# remote_display.net
KiCad netlist of a schematic drawn in EAGLE
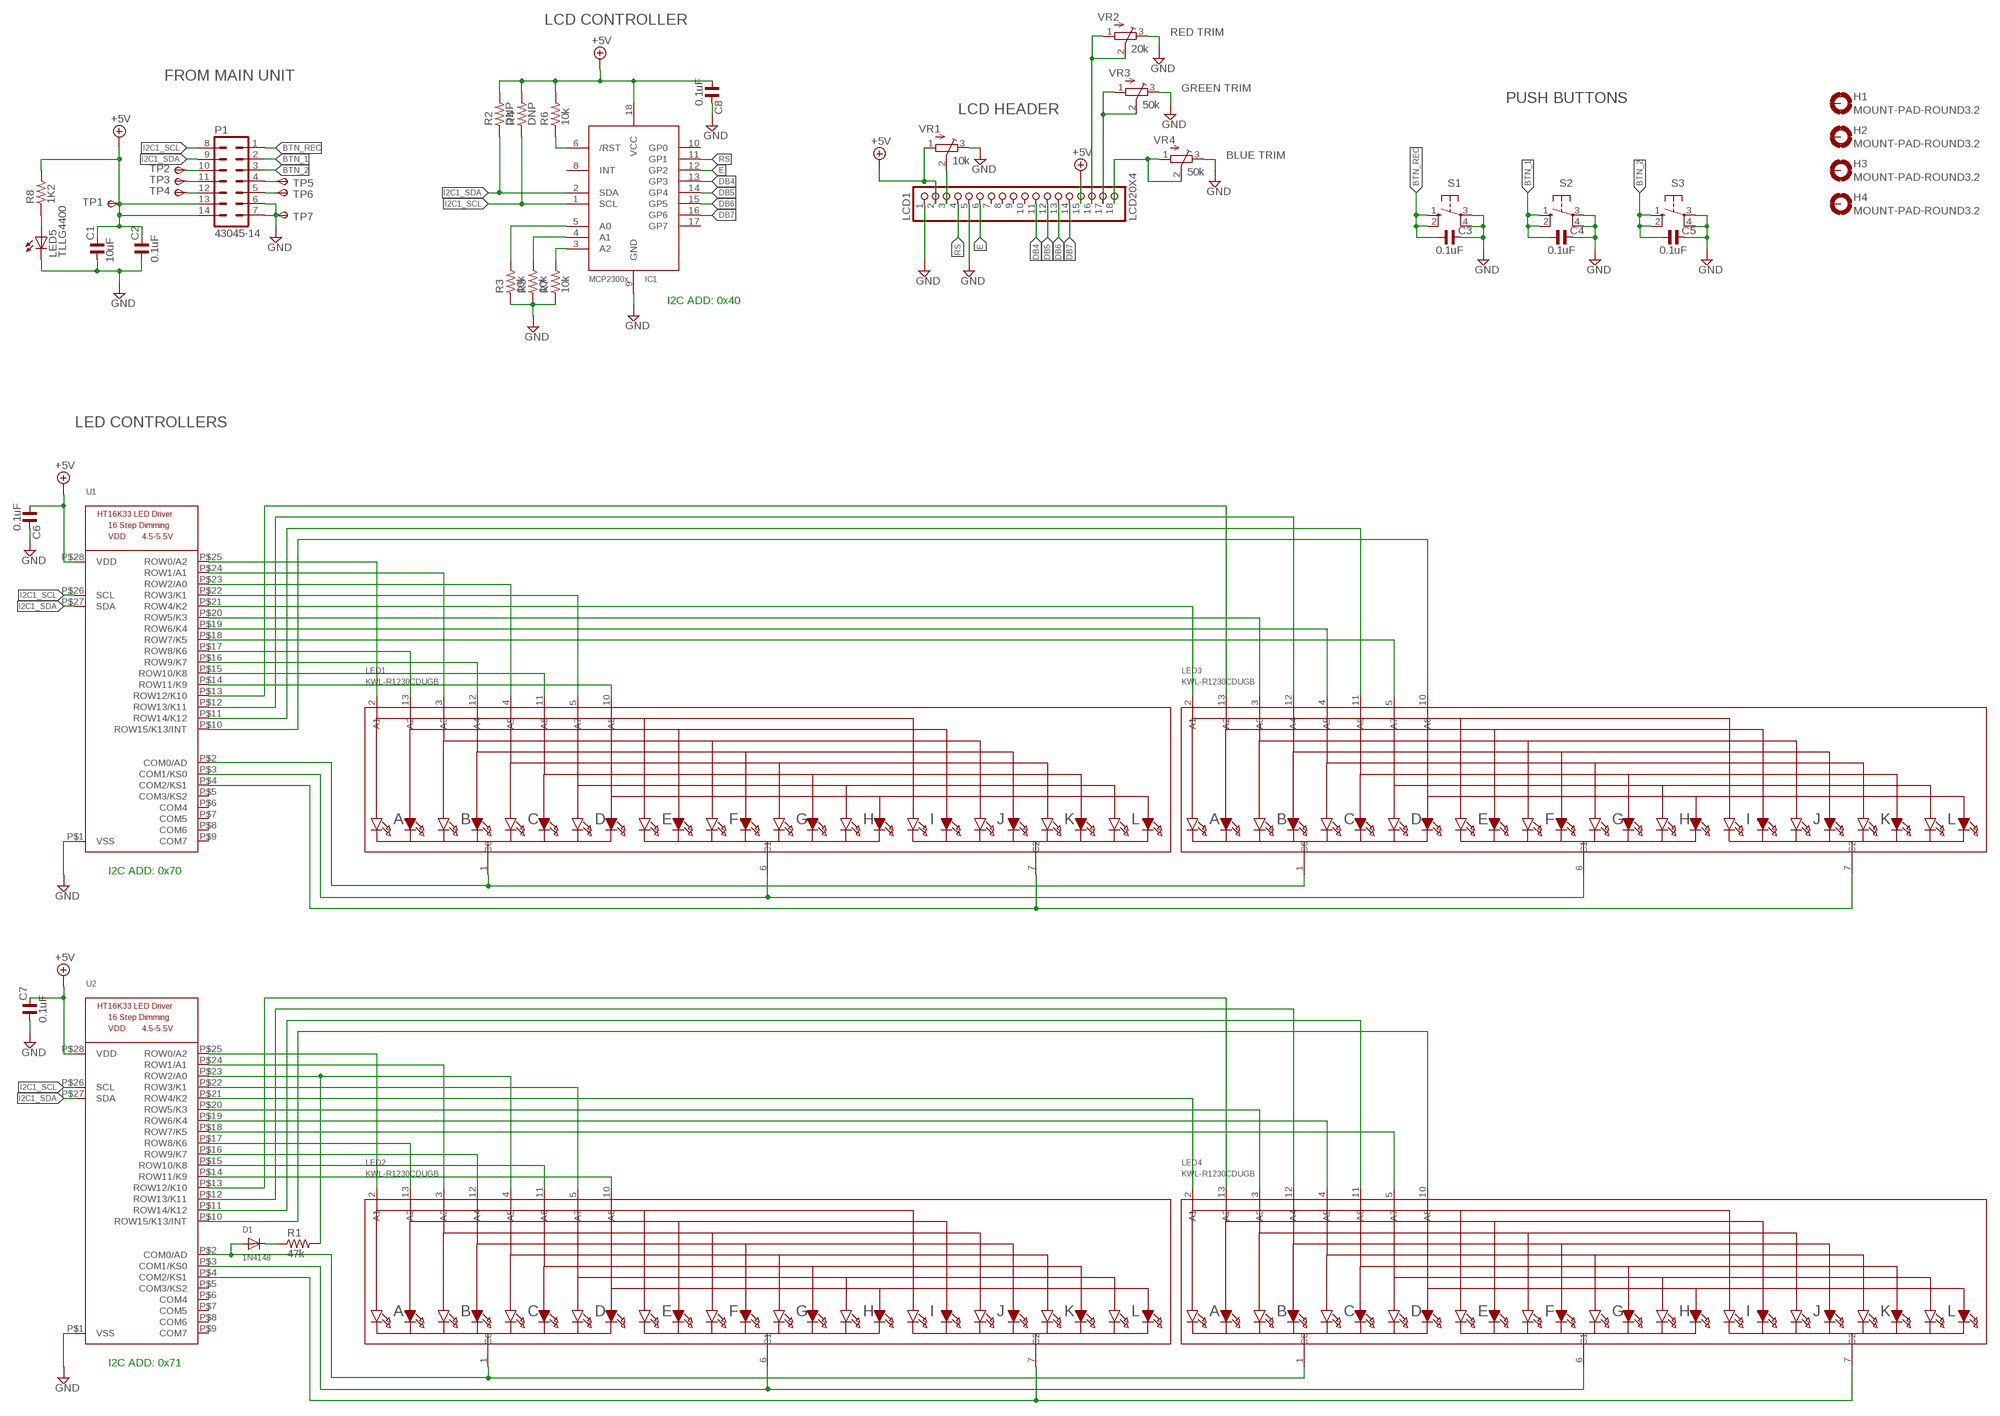
[diagram p0: schematic, sheet 1]

(export (version "E")
  (design (tool "Eeschema 10.0.6"))
  (components
    (comp (ref "C1")
      (value "10uF")
      (footprint "eagle-import:C0805")
      (fields (field (name "MPN") "C2012X5R1E106K125AB"))
      (libsource (lib "eagle-import") (part "C_0805"))
    )
    (comp (ref "C2")
      (value "0.1uF")
      (footprint "eagle-import:C0805")
      (fields (field (name "MPN") "C2012X7R1H104K085AA"))
      (libsource (lib "eagle-import") (part "C_0805"))
    )
    (comp (ref "C3")
      (value "0.1uF")
      (footprint "eagle-import:C0805")
      (fields (field (name "MPN") "C2012X7R1H104K085AA"))
      (libsource (lib "eagle-import") (part "C_0805"))
    )
    (comp (ref "C4")
      (value "0.1uF")
      (footprint "eagle-import:C0805")
      (fields (field (name "MPN") "C2012X7R1H104K085AA"))
      (libsource (lib "eagle-import") (part "C_0805"))
    )
    (comp (ref "C5")
      (value "0.1uF")
      (footprint "eagle-import:C0805")
      (fields (field (name "MPN") "C2012X7R1H104K085AA"))
      (libsource (lib "eagle-import") (part "C_0805"))
    )
    (comp (ref "C6")
      (value "0.1uF")
      (footprint "eagle-import:C0805")
      (fields (field (name "MPN") "C2012X7R1H104K085AA"))
      (libsource (lib "eagle-import") (part "C_0805"))
    )
    (comp (ref "C7")
      (value "0.1uF")
      (footprint "eagle-import:C0805")
      (fields (field (name "MPN") "C2012X7R1H104K085AA"))
      (libsource (lib "eagle-import") (part "C_0805"))
    )
    (comp (ref "C8")
      (value "0.1uF")
      (footprint "eagle-import:C0805")
      (fields (field (name "MPN") "C2012X7R1H104K085AA"))
      (libsource (lib "eagle-import") (part "C_0805"))
    )
    (comp (ref "D1")
      (value "1N4148")
      (footprint "eagle-import:SOD-323F")
      (fields (field (name "MPN") "MMBT2222ALT3G"))
      (libsource (lib "eagle-import") (part "DIODESOD-323F"))
    )
    (comp (ref "H1")
      (value "MOUNT-PAD-ROUND3.2")
      (footprint "eagle-import:3,2-PAD")
      (libsource (lib "eagle-import") (part "MOUNT-PAD-ROUND3.2"))
    )
    (comp (ref "H2")
      (value "MOUNT-PAD-ROUND3.2")
      (footprint "eagle-import:3,2-PAD")
      (libsource (lib "eagle-import") (part "MOUNT-PAD-ROUND3.2"))
    )
    (comp (ref "H3")
      (value "MOUNT-PAD-ROUND3.2")
      (footprint "eagle-import:3,2-PAD")
      (libsource (lib "eagle-import") (part "MOUNT-PAD-ROUND3.2"))
    )
    (comp (ref "H4")
      (value "MOUNT-PAD-ROUND3.2")
      (footprint "eagle-import:3,2-PAD")
      (libsource (lib "eagle-import") (part "MOUNT-PAD-ROUND3.2"))
    )
    (comp (ref "IC1")
      (value "MCP2300X/SO")
      (footprint "eagle-import:SO18W")
      (fields (field (name "MF") "MICROCHIP") (field (name "MPN") "MCP23008-E/SO"))
      (libsource (lib "eagle-import") (part "MCP2300X/SO"))
    )
    (comp (ref "LCD1")
      (value "LCD20X4")
      (footprint "eagle-import:LCD20X4")
      (libsource (lib "eagle-import") (part "LCD20X4"))
    )
    (comp (ref "LED1")
      (value "KWL-R1230CDUGB")
      (footprint "eagle-import:SEGMENT_BICOL_BL-AR12Z3010")
      (libsource (lib "eagle-import") (part "KWL-R1230CDUGB"))
    )
    (comp (ref "LED2")
      (value "KWL-R1230CDUGB")
      (footprint "eagle-import:SEGMENT_BICOL_BL-AR12Z3010")
      (libsource (lib "eagle-import") (part "KWL-R1230CDUGB"))
    )
    (comp (ref "LED3")
      (value "KWL-R1230CDUGB")
      (footprint "eagle-import:SEGMENT_BICOL_BL-AR12Z3010")
      (libsource (lib "eagle-import") (part "KWL-R1230CDUGB"))
    )
    (comp (ref "LED4")
      (value "KWL-R1230CDUGB")
      (footprint "eagle-import:SEGMENT_BICOL_BL-AR12Z3010")
      (libsource (lib "eagle-import") (part "KWL-R1230CDUGB"))
    )
    (comp (ref "LED5")
      (value "TLLG4400")
      (footprint "eagle-import:LED3MM")
      (fields (field (name "MF") "VISHAY SEMICONDUCTOR") (field (name "MF_1") "VISHAY/TELEFUNKEN"))
      (libsource (lib "eagle-import") (part "TLLG4400"))
    )
    (comp (ref "P1")
      (value "43045-14")
      (footprint "eagle-import:43045-14")
      (fields (field (name "MPN") "43045-1400"))
      (libsource (lib "eagle-import") (part "43045-14"))
    )
    (comp (ref "R1")
      (value "47k")
      (footprint "eagle-import:R0805")
      (fields (field (name "MPN") "CRCW080547K0FKEAHP"))
      (libsource (lib "eagle-import") (part "R_0805"))
    )
    (comp (ref "R2")
      (value "DNP")
      (footprint "eagle-import:R0805")
      (fields (field (name "MF") "VISHAY/DALE") (field (name "MPN") "CRCW080510K0FKTA"))
      (libsource (lib "eagle-import") (part "R_0805"))
    )
    (comp (ref "R3")
      (value "10k")
      (footprint "eagle-import:R0805")
      (fields (field (name "MF") "VISHAY/DALE") (field (name "MPN") "CRCW080510K0FKTA"))
      (libsource (lib "eagle-import") (part "R_0805"))
    )
    (comp (ref "R4")
      (value "DNP")
      (footprint "eagle-import:R0805")
      (fields (field (name "MF") "VISHAY/DALE") (field (name "MPN") "CRCW080510K0FKTA"))
      (libsource (lib "eagle-import") (part "R_0805"))
    )
    (comp (ref "R5")
      (value "10k")
      (footprint "eagle-import:R0805")
      (fields (field (name "MF") "VISHAY/DALE") (field (name "MPN") "CRCW080510K0FKTA"))
      (libsource (lib "eagle-import") (part "R_0805"))
    )
    (comp (ref "R6")
      (value "10k")
      (footprint "eagle-import:R0805")
      (fields (field (name "MF") "VISHAY/DALE") (field (name "MPN") "CRCW080510K0FKTA"))
      (libsource (lib "eagle-import") (part "R_0805"))
    )
    (comp (ref "R7")
      (value "10k")
      (footprint "eagle-import:R0805")
      (fields (field (name "MF") "VISHAY/DALE") (field (name "MPN") "CRCW080510K0FKTA"))
      (libsource (lib "eagle-import") (part "R_0805"))
    )
    (comp (ref "R8")
      (value "1K2")
      (footprint "eagle-import:R0805")
      (fields (field (name "MF") "VISHAY/DALE") (field (name "MPN") "CRCW080510K0FKTA"))
      (libsource (lib "eagle-import") (part "R_0805"))
    )
    (comp (ref "S1")
      (value "10-XX")
      (footprint "eagle-import:B3F-10XX")
      (fields (field (name "MPN") "B3F-1000") (field (name "OC_NEWARK") "unknown"))
      (libsource (lib "eagle-import") (part "10-XX"))
    )
    (comp (ref "S2")
      (value "10-XX")
      (footprint "eagle-import:B3F-10XX")
      (fields (field (name "MPN") "B3F-1000") (field (name "OC_NEWARK") "unknown"))
      (libsource (lib "eagle-import") (part "10-XX"))
    )
    (comp (ref "S3")
      (value "10-XX")
      (footprint "eagle-import:B3F-10XX")
      (fields (field (name "MPN") "B3F-1000") (field (name "OC_NEWARK") "unknown"))
      (libsource (lib "eagle-import") (part "10-XX"))
    )
    (comp (ref "TP1")
      (value "TPSPAD1-13")
      (footprint "eagle-import:P1-13")
      (libsource (lib "eagle-import") (part "TPSPAD1-13"))
    )
    (comp (ref "TP2")
      (value "TPSPAD1-13")
      (footprint "eagle-import:P1-13")
      (libsource (lib "eagle-import") (part "TPSPAD1-13"))
    )
    (comp (ref "TP3")
      (value "TPSPAD1-13")
      (footprint "eagle-import:P1-13")
      (libsource (lib "eagle-import") (part "TPSPAD1-13"))
    )
    (comp (ref "TP4")
      (value "TPSPAD1-13")
      (footprint "eagle-import:P1-13")
      (libsource (lib "eagle-import") (part "TPSPAD1-13"))
    )
    (comp (ref "TP5")
      (value "TPSPAD1-13")
      (footprint "eagle-import:P1-13")
      (libsource (lib "eagle-import") (part "TPSPAD1-13"))
    )
    (comp (ref "TP6")
      (value "TPSPAD1-13")
      (footprint "eagle-import:P1-13")
      (libsource (lib "eagle-import") (part "TPSPAD1-13"))
    )
    (comp (ref "TP7")
      (value "TPSPAD1-13")
      (footprint "eagle-import:P1-13")
      (libsource (lib "eagle-import") (part "TPSPAD1-13"))
    )
    (comp (ref "U1")
      (value "HT16K33_SOP28")
      (footprint "eagle-import:SOP28_300MIL")
      (libsource (lib "eagle-import") (part "HT16K33_SOP28"))
    )
    (comp (ref "U2")
      (value "HT16K33_SOP28")
      (footprint "eagle-import:SOP28_300MIL")
      (libsource (lib "eagle-import") (part "HT16K33_SOP28"))
    )
    (comp (ref "VR1")
      (value "10k")
      (footprint "eagle-import:TC33X")
      (fields (field (name "MF") "BOURNS, INC.") (field (name "MPN") "TC33X-2-103E"))
      (libsource (lib "eagle-import") (part "TRIMPOTTC33X"))
    )
    (comp (ref "VR2")
      (value "20k")
      (footprint "eagle-import:TC33X")
      (fields (field (name "MPN") "TC33X-2-203E"))
      (libsource (lib "eagle-import") (part "TRIMPOTTC33X"))
    )
    (comp (ref "VR3")
      (value "50k")
      (footprint "eagle-import:TC33X")
      (fields (field (name "MPN") "TC33X-2-503E"))
      (libsource (lib "eagle-import") (part "TRIMPOTTC33X"))
    )
    (comp (ref "VR4")
      (value "50k")
      (footprint "eagle-import:TC33X")
      (fields (field (name "MPN") "TC33X-2-503E"))
      (libsource (lib "eagle-import") (part "TRIMPOTTC33X"))
    )
  )
  (nets
    (net (code "1") (name "+5V") (class "Default")
      (node (ref "C1") (pin "2") (pinfunction "2_2") (pintype "passive"))
      (node (ref "C2") (pin "2") (pinfunction "2_2") (pintype "passive"))
      (node (ref "C6") (pin "1") (pinfunction "1_1") (pintype "passive"))
      (node (ref "C7") (pin "2") (pinfunction "2_2") (pintype "passive"))
      (node (ref "C8") (pin "1") (pinfunction "1_1") (pintype "passive"))
      (node (ref "IC1") (pin "18") (pinfunction "VCC_18") (pintype "power_in"))
      (node (ref "LCD1") (pin "15") (pinfunction "15_15") (pintype "passive"))
      (node (ref "LCD1") (pin "2") (pinfunction "2_2") (pintype "passive"))
      (node (ref "P1") (pin "13") (pinfunction "13_13") (pintype "passive"))
      (node (ref "P1") (pin "14") (pinfunction "14_14") (pintype "passive"))
      (node (ref "R2") (pin "2") (pinfunction "2_2") (pintype "passive"))
      (node (ref "R4") (pin "2") (pinfunction "2_2") (pintype "passive"))
      (node (ref "R6") (pin "2") (pinfunction "2_2") (pintype "passive"))
      (node (ref "R8") (pin "2") (pinfunction "2_2") (pintype "passive"))
      (node (ref "TP1") (pin "TP") (pinfunction "PP_TP") (pintype "input"))
      (node (ref "U1") (pin "P$28") (pinfunction "VDD_P$28") (pintype "bidirectional"))
      (node (ref "U2") (pin "P$28") (pinfunction "VDD_P$28") (pintype "bidirectional"))
      (node (ref "VR1") (pin "1") (pinfunction "A_1") (pintype "passive"))
    )
    (net (code "2") (name "BTN_1") (class "Default")
      (node (ref "C4") (pin "1") (pinfunction "1_1") (pintype "passive"))
      (node (ref "P1") (pin "2") (pinfunction "2_2") (pintype "passive"))
      (node (ref "S2") (pin "1") (pinfunction "S_1") (pintype "passive"))
      (node (ref "S2") (pin "2") (pinfunction "S1_2") (pintype "passive"))
    )
    (net (code "3") (name "BTN_2") (class "Default")
      (node (ref "C5") (pin "1") (pinfunction "1_1") (pintype "passive"))
      (node (ref "P1") (pin "3") (pinfunction "3_3") (pintype "passive"))
      (node (ref "S3") (pin "1") (pinfunction "S_1") (pintype "passive"))
      (node (ref "S3") (pin "2") (pinfunction "S1_2") (pintype "passive"))
    )
    (net (code "4") (name "BTN_REC") (class "Default")
      (node (ref "C3") (pin "1") (pinfunction "1_1") (pintype "passive"))
      (node (ref "P1") (pin "1") (pinfunction "1_1") (pintype "passive"))
      (node (ref "S1") (pin "1") (pinfunction "S_1") (pintype "passive"))
      (node (ref "S1") (pin "2") (pinfunction "S1_2") (pintype "passive"))
    )
    (net (code "5") (name "DB4") (class "Default")
      (node (ref "IC1") (pin "13") (pinfunction "GP3_13") (pintype "bidirectional"))
      (node (ref "LCD1") (pin "11") (pinfunction "11_11") (pintype "passive"))
    )
    (net (code "6") (name "DB5") (class "Default")
      (node (ref "IC1") (pin "14") (pinfunction "GP4_14") (pintype "bidirectional"))
      (node (ref "LCD1") (pin "12") (pinfunction "12_12") (pintype "passive"))
    )
    (net (code "7") (name "DB6") (class "Default")
      (node (ref "IC1") (pin "15") (pinfunction "GP5_15") (pintype "bidirectional"))
      (node (ref "LCD1") (pin "13") (pinfunction "13_13") (pintype "passive"))
    )
    (net (code "8") (name "DB7") (class "Default")
      (node (ref "IC1") (pin "16") (pinfunction "GP6_16") (pintype "bidirectional"))
      (node (ref "LCD1") (pin "14") (pinfunction "14_14") (pintype "passive"))
    )
    (net (code "9") (name "E") (class "Default")
      (node (ref "IC1") (pin "12") (pinfunction "GP2_12") (pintype "bidirectional"))
      (node (ref "LCD1") (pin "6") (pinfunction "6_6") (pintype "passive"))
    )
    (net (code "10") (name "GND") (class "Default")
      (node (ref "C1") (pin "1") (pinfunction "1_1") (pintype "passive"))
      (node (ref "C2") (pin "1") (pinfunction "1_1") (pintype "passive"))
      (node (ref "C3") (pin "2") (pinfunction "2_2") (pintype "passive"))
      (node (ref "C4") (pin "2") (pinfunction "2_2") (pintype "passive"))
      (node (ref "C5") (pin "2") (pinfunction "2_2") (pintype "passive"))
      (node (ref "C6") (pin "2") (pinfunction "2_2") (pintype "passive"))
      (node (ref "C7") (pin "1") (pinfunction "1_1") (pintype "passive"))
      (node (ref "C8") (pin "2") (pinfunction "2_2") (pintype "passive"))
      (node (ref "IC1") (pin "9") (pinfunction "GND_9") (pintype "power_in"))
      (node (ref "LCD1") (pin "1") (pinfunction "1_1") (pintype "passive"))
      (node (ref "LCD1") (pin "5") (pinfunction "5_5") (pintype "passive"))
      (node (ref "LED5") (pin "K") (pinfunction "C_K") (pintype "passive"))
      (node (ref "P1") (pin "6") (pinfunction "6_6") (pintype "passive"))
      (node (ref "P1") (pin "7") (pinfunction "7_7") (pintype "passive"))
      (node (ref "R3") (pin "1") (pinfunction "1_1") (pintype "passive"))
      (node (ref "R5") (pin "1") (pinfunction "1_1") (pintype "passive"))
      (node (ref "R7") (pin "1") (pinfunction "1_1") (pintype "passive"))
      (node (ref "S1") (pin "3") (pinfunction "P_3") (pintype "passive"))
      (node (ref "S1") (pin "4") (pinfunction "P1_4") (pintype "passive"))
      (node (ref "S2") (pin "3") (pinfunction "P_3") (pintype "passive"))
      (node (ref "S2") (pin "4") (pinfunction "P1_4") (pintype "passive"))
      (node (ref "S3") (pin "3") (pinfunction "P_3") (pintype "passive"))
      (node (ref "S3") (pin "4") (pinfunction "P1_4") (pintype "passive"))
      (node (ref "TP7") (pin "TP") (pinfunction "PP_TP") (pintype "input"))
      (node (ref "U1") (pin "P$1") (pinfunction "VSS_P$1") (pintype "bidirectional"))
      (node (ref "U2") (pin "P$1") (pinfunction "VSS_P$1") (pintype "bidirectional"))
      (node (ref "VR1") (pin "3") (pinfunction "E_3") (pintype "passive"))
      (node (ref "VR2") (pin "3") (pinfunction "E_3") (pintype "passive"))
      (node (ref "VR3") (pin "3") (pinfunction "E_3") (pintype "passive"))
      (node (ref "VR4") (pin "3") (pinfunction "E_3") (pintype "passive"))
    )
    (net (code "11") (name "I2C1_SCL") (class "Default")
      (node (ref "IC1") (pin "1") (pinfunction "SCL_1") (pintype "bidirectional"))
      (node (ref "P1") (pin "8") (pinfunction "8_8") (pintype "passive"))
      (node (ref "R4") (pin "1") (pinfunction "1_1") (pintype "passive"))
      (node (ref "U1") (pin "P$26") (pinfunction "SCL_P$26") (pintype "bidirectional"))
      (node (ref "U2") (pin "P$26") (pinfunction "SCL_P$26") (pintype "bidirectional"))
    )
    (net (code "12") (name "I2C1_SDA") (class "Default")
      (node (ref "IC1") (pin "2") (pinfunction "SDA_2") (pintype "bidirectional"))
      (node (ref "P1") (pin "9") (pinfunction "9_9") (pintype "passive"))
      (node (ref "R2") (pin "1") (pinfunction "1_1") (pintype "passive"))
      (node (ref "U1") (pin "P$27") (pinfunction "SDA_P$27") (pintype "bidirectional"))
      (node (ref "U2") (pin "P$27") (pinfunction "SDA_P$27") (pintype "bidirectional"))
    )
    (net (code "13") (name "Net-(D1-PadC)") (class "Default")
      (node (ref "D1") (pin "C") (pinfunction "C_C") (pintype "passive"))
      (node (ref "R1") (pin "1") (pinfunction "1_1") (pintype "passive"))
    )
    (net (code "14") (name "Net-(IC1-A0)") (class "Default")
      (node (ref "IC1") (pin "5") (pinfunction "A0_5") (pintype "input"))
      (node (ref "R3") (pin "2") (pinfunction "2_2") (pintype "passive"))
    )
    (net (code "15") (name "Net-(IC1-A1)") (class "Default")
      (node (ref "IC1") (pin "4") (pinfunction "A1_4") (pintype "input"))
      (node (ref "R5") (pin "2") (pinfunction "2_2") (pintype "passive"))
    )
    (net (code "16") (name "Net-(IC1-A2)") (class "Default")
      (node (ref "IC1") (pin "3") (pinfunction "A2_3") (pintype "input"))
      (node (ref "R7") (pin "2") (pinfunction "2_2") (pintype "passive"))
    )
    (net (code "17") (name "Net-(IC1-{slash}RST)") (class "Default")
      (node (ref "IC1") (pin "6") (pinfunction "/RST_6") (pintype "input"))
      (node (ref "R6") (pin "1") (pinfunction "1_1") (pintype "passive"))
    )
    (net (code "18") (name "Net-(LED1-A1)") (class "Default")
      (node (ref "LED1") (pin "2") (pinfunction "A1_2") (pintype "bidirectional"))
      (node (ref "U1") (pin "P$25") (pinfunction "ROW0/A2_P$25") (pintype "bidirectional"))
    )
    (net (code "19") (name "Net-(LED1-A2)") (class "Default")
      (node (ref "LED1") (pin "13") (pinfunction "A2_13") (pintype "bidirectional"))
      (node (ref "U1") (pin "P$17") (pinfunction "ROW8/K6_P$17") (pintype "bidirectional"))
    )
    (net (code "20") (name "Net-(LED1-A3)") (class "Default")
      (node (ref "LED1") (pin "3") (pinfunction "A3_3") (pintype "bidirectional"))
      (node (ref "U1") (pin "P$24") (pinfunction "ROW1/A1_P$24") (pintype "bidirectional"))
    )
    (net (code "21") (name "Net-(LED1-A4)") (class "Default")
      (node (ref "LED1") (pin "12") (pinfunction "A4_12") (pintype "bidirectional"))
      (node (ref "U1") (pin "P$16") (pinfunction "ROW9/K7_P$16") (pintype "bidirectional"))
    )
    (net (code "22") (name "Net-(LED1-A5)") (class "Default")
      (node (ref "LED1") (pin "4") (pinfunction "A5_4") (pintype "bidirectional"))
      (node (ref "U1") (pin "P$23") (pinfunction "ROW2/A0_P$23") (pintype "bidirectional"))
    )
    (net (code "23") (name "Net-(LED1-A6)") (class "Default")
      (node (ref "LED1") (pin "11") (pinfunction "A6_11") (pintype "bidirectional"))
      (node (ref "U1") (pin "P$15") (pinfunction "ROW10/K8_P$15") (pintype "bidirectional"))
    )
    (net (code "24") (name "Net-(LED1-A7)") (class "Default")
      (node (ref "LED1") (pin "5") (pinfunction "A7_5") (pintype "bidirectional"))
      (node (ref "U1") (pin "P$22") (pinfunction "ROW3/K1_P$22") (pintype "bidirectional"))
    )
    (net (code "25") (name "Net-(LED1-A8)") (class "Default")
      (node (ref "LED1") (pin "10") (pinfunction "A8_10") (pintype "bidirectional"))
      (node (ref "U1") (pin "P$14") (pinfunction "ROW11/K9_P$14") (pintype "bidirectional"))
    )
    (net (code "26") (name "Net-(LED1-C0)") (class "Default")
      (node (ref "LED1") (pin "1") (pinfunction "C0_1") (pintype "bidirectional"))
      (node (ref "LED3") (pin "1") (pinfunction "C0_1") (pintype "bidirectional"))
      (node (ref "U1") (pin "P$2") (pinfunction "COM0/AD_P$2") (pintype "bidirectional"))
    )
    (net (code "27") (name "Net-(LED1-C1)") (class "Default")
      (node (ref "LED1") (pin "6") (pinfunction "C1_6") (pintype "bidirectional"))
      (node (ref "LED3") (pin "6") (pinfunction "C1_6") (pintype "bidirectional"))
      (node (ref "U1") (pin "P$3") (pinfunction "COM1/KS0_P$3") (pintype "bidirectional"))
    )
    (net (code "28") (name "Net-(LED1-C2)") (class "Default")
      (node (ref "LED1") (pin "7") (pinfunction "C2_7") (pintype "bidirectional"))
      (node (ref "LED3") (pin "7") (pinfunction "C2_7") (pintype "bidirectional"))
      (node (ref "U1") (pin "P$4") (pinfunction "COM2/KS1_P$4") (pintype "bidirectional"))
    )
    (net (code "29") (name "Net-(LED2-A1)") (class "Default")
      (node (ref "LED2") (pin "2") (pinfunction "A1_2") (pintype "bidirectional"))
      (node (ref "U2") (pin "P$25") (pinfunction "ROW0/A2_P$25") (pintype "bidirectional"))
    )
    (net (code "30") (name "Net-(LED2-A2)") (class "Default")
      (node (ref "LED2") (pin "13") (pinfunction "A2_13") (pintype "bidirectional"))
      (node (ref "U2") (pin "P$17") (pinfunction "ROW8/K6_P$17") (pintype "bidirectional"))
    )
    (net (code "31") (name "Net-(LED2-A3)") (class "Default")
      (node (ref "LED2") (pin "3") (pinfunction "A3_3") (pintype "bidirectional"))
      (node (ref "U2") (pin "P$24") (pinfunction "ROW1/A1_P$24") (pintype "bidirectional"))
    )
    (net (code "32") (name "Net-(LED2-A4)") (class "Default")
      (node (ref "LED2") (pin "12") (pinfunction "A4_12") (pintype "bidirectional"))
      (node (ref "U2") (pin "P$16") (pinfunction "ROW9/K7_P$16") (pintype "bidirectional"))
    )
    (net (code "33") (name "Net-(LED2-A5)") (class "Default")
      (node (ref "LED2") (pin "4") (pinfunction "A5_4") (pintype "bidirectional"))
      (node (ref "R1") (pin "2") (pinfunction "2_2") (pintype "passive"))
      (node (ref "U2") (pin "P$23") (pinfunction "ROW2/A0_P$23") (pintype "bidirectional"))
    )
    (net (code "34") (name "Net-(LED2-A6)") (class "Default")
      (node (ref "LED2") (pin "11") (pinfunction "A6_11") (pintype "bidirectional"))
      (node (ref "U2") (pin "P$15") (pinfunction "ROW10/K8_P$15") (pintype "bidirectional"))
    )
    (net (code "35") (name "Net-(LED2-A7)") (class "Default")
      (node (ref "LED2") (pin "5") (pinfunction "A7_5") (pintype "bidirectional"))
      (node (ref "U2") (pin "P$22") (pinfunction "ROW3/K1_P$22") (pintype "bidirectional"))
    )
    (net (code "36") (name "Net-(LED2-A8)") (class "Default")
      (node (ref "LED2") (pin "10") (pinfunction "A8_10") (pintype "bidirectional"))
      (node (ref "U2") (pin "P$14") (pinfunction "ROW11/K9_P$14") (pintype "bidirectional"))
    )
    (net (code "37") (name "Net-(LED2-C0)") (class "Default")
      (node (ref "D1") (pin "A") (pinfunction "A_A") (pintype "passive"))
      (node (ref "LED2") (pin "1") (pinfunction "C0_1") (pintype "bidirectional"))
      (node (ref "LED4") (pin "1") (pinfunction "C0_1") (pintype "bidirectional"))
      (node (ref "U2") (pin "P$2") (pinfunction "COM0/AD_P$2") (pintype "bidirectional"))
    )
    (net (code "38") (name "Net-(LED2-C1)") (class "Default")
      (node (ref "LED2") (pin "6") (pinfunction "C1_6") (pintype "bidirectional"))
      (node (ref "LED4") (pin "6") (pinfunction "C1_6") (pintype "bidirectional"))
      (node (ref "U2") (pin "P$3") (pinfunction "COM1/KS0_P$3") (pintype "bidirectional"))
    )
    (net (code "39") (name "Net-(LED2-C2)") (class "Default")
      (node (ref "LED2") (pin "7") (pinfunction "C2_7") (pintype "bidirectional"))
      (node (ref "LED4") (pin "7") (pinfunction "C2_7") (pintype "bidirectional"))
      (node (ref "U2") (pin "P$4") (pinfunction "COM2/KS1_P$4") (pintype "bidirectional"))
    )
    (net (code "40") (name "Net-(LED3-A1)") (class "Default")
      (node (ref "LED3") (pin "2") (pinfunction "A1_2") (pintype "bidirectional"))
      (node (ref "U1") (pin "P$21") (pinfunction "ROW4/K2_P$21") (pintype "bidirectional"))
    )
    (net (code "41") (name "Net-(LED3-A2)") (class "Default")
      (node (ref "LED3") (pin "13") (pinfunction "A2_13") (pintype "bidirectional"))
      (node (ref "U1") (pin "P$13") (pinfunction "ROW12/K10_P$13") (pintype "bidirectional"))
    )
    (net (code "42") (name "Net-(LED3-A3)") (class "Default")
      (node (ref "LED3") (pin "3") (pinfunction "A3_3") (pintype "bidirectional"))
      (node (ref "U1") (pin "P$20") (pinfunction "ROW5/K3_P$20") (pintype "bidirectional"))
    )
    (net (code "43") (name "Net-(LED3-A4)") (class "Default")
      (node (ref "LED3") (pin "12") (pinfunction "A4_12") (pintype "bidirectional"))
      (node (ref "U1") (pin "P$12") (pinfunction "ROW13/K11_P$12") (pintype "bidirectional"))
    )
    (net (code "44") (name "Net-(LED3-A5)") (class "Default")
      (node (ref "LED3") (pin "4") (pinfunction "A5_4") (pintype "bidirectional"))
      (node (ref "U1") (pin "P$19") (pinfunction "ROW6/K4_P$19") (pintype "bidirectional"))
    )
    (net (code "45") (name "Net-(LED3-A6)") (class "Default")
      (node (ref "LED3") (pin "11") (pinfunction "A6_11") (pintype "bidirectional"))
      (node (ref "U1") (pin "P$11") (pinfunction "ROW14/K12_P$11") (pintype "bidirectional"))
    )
    (net (code "46") (name "Net-(LED3-A7)") (class "Default")
      (node (ref "LED3") (pin "5") (pinfunction "A7_5") (pintype "bidirectional"))
      (node (ref "U1") (pin "P$18") (pinfunction "ROW7/K5_P$18") (pintype "bidirectional"))
    )
    (net (code "47") (name "Net-(LED3-A8)") (class "Default")
      (node (ref "LED3") (pin "10") (pinfunction "A8_10") (pintype "bidirectional"))
      (node (ref "U1") (pin "P$10") (pinfunction "ROW15/K13/INT_P$10") (pintype "bidirectional"))
    )
    (net (code "48") (name "Net-(LED4-A1)") (class "Default")
      (node (ref "LED4") (pin "2") (pinfunction "A1_2") (pintype "bidirectional"))
      (node (ref "U2") (pin "P$21") (pinfunction "ROW4/K2_P$21") (pintype "bidirectional"))
    )
    (net (code "49") (name "Net-(LED4-A2)") (class "Default")
      (node (ref "LED4") (pin "13") (pinfunction "A2_13") (pintype "bidirectional"))
      (node (ref "U2") (pin "P$13") (pinfunction "ROW12/K10_P$13") (pintype "bidirectional"))
    )
    (net (code "50") (name "Net-(LED4-A3)") (class "Default")
      (node (ref "LED4") (pin "3") (pinfunction "A3_3") (pintype "bidirectional"))
      (node (ref "U2") (pin "P$20") (pinfunction "ROW5/K3_P$20") (pintype "bidirectional"))
    )
    (net (code "51") (name "Net-(LED4-A4)") (class "Default")
      (node (ref "LED4") (pin "12") (pinfunction "A4_12") (pintype "bidirectional"))
      (node (ref "U2") (pin "P$12") (pinfunction "ROW13/K11_P$12") (pintype "bidirectional"))
    )
    (net (code "52") (name "Net-(LED4-A5)") (class "Default")
      (node (ref "LED4") (pin "4") (pinfunction "A5_4") (pintype "bidirectional"))
      (node (ref "U2") (pin "P$19") (pinfunction "ROW6/K4_P$19") (pintype "bidirectional"))
    )
    (net (code "53") (name "Net-(LED4-A6)") (class "Default")
      (node (ref "LED4") (pin "11") (pinfunction "A6_11") (pintype "bidirectional"))
      (node (ref "U2") (pin "P$11") (pinfunction "ROW14/K12_P$11") (pintype "bidirectional"))
    )
    (net (code "54") (name "Net-(LED4-A7)") (class "Default")
      (node (ref "LED4") (pin "5") (pinfunction "A7_5") (pintype "bidirectional"))
      (node (ref "U2") (pin "P$18") (pinfunction "ROW7/K5_P$18") (pintype "bidirectional"))
    )
    (net (code "55") (name "Net-(LED4-A8)") (class "Default")
      (node (ref "LED4") (pin "10") (pinfunction "A8_10") (pintype "bidirectional"))
      (node (ref "U2") (pin "P$10") (pinfunction "ROW15/K13/INT_P$10") (pintype "bidirectional"))
    )
    (net (code "56") (name "Net-(LED5-PadA)") (class "Default")
      (node (ref "LED5") (pin "A") (pinfunction "A_A") (pintype "passive"))
      (node (ref "R8") (pin "1") (pinfunction "1_1") (pintype "passive"))
    )
    (net (code "57") (name "Net-(TP2-PP)") (class "Default")
      (node (ref "P1") (pin "10") (pinfunction "10_10") (pintype "passive"))
      (node (ref "TP2") (pin "TP") (pinfunction "PP_TP") (pintype "input"))
    )
    (net (code "58") (name "Net-(TP3-PP)") (class "Default")
      (node (ref "P1") (pin "11") (pinfunction "11_11") (pintype "passive"))
      (node (ref "TP3") (pin "TP") (pinfunction "PP_TP") (pintype "input"))
    )
    (net (code "59") (name "Net-(TP4-PP)") (class "Default")
      (node (ref "P1") (pin "12") (pinfunction "12_12") (pintype "passive"))
      (node (ref "TP4") (pin "TP") (pinfunction "PP_TP") (pintype "input"))
    )
    (net (code "60") (name "Net-(TP5-PP)") (class "Default")
      (node (ref "P1") (pin "4") (pinfunction "4_4") (pintype "passive"))
      (node (ref "TP5") (pin "TP") (pinfunction "PP_TP") (pintype "input"))
    )
    (net (code "61") (name "Net-(TP6-PP)") (class "Default")
      (node (ref "P1") (pin "5") (pinfunction "5_5") (pintype "passive"))
      (node (ref "TP6") (pin "TP") (pinfunction "PP_TP") (pintype "input"))
    )
    (net (code "62") (name "Net-(VR1-S)") (class "Default")
      (node (ref "LCD1") (pin "3") (pinfunction "3_3") (pintype "passive"))
      (node (ref "VR1") (pin "2") (pinfunction "S_2") (pintype "passive"))
    )
    (net (code "63") (name "Net-(VR2-A)") (class "Default")
      (node (ref "LCD1") (pin "16") (pinfunction "16_16") (pintype "passive"))
      (node (ref "VR2") (pin "1") (pinfunction "A_1") (pintype "passive"))
      (node (ref "VR2") (pin "2") (pinfunction "S_2") (pintype "passive"))
    )
    (net (code "64") (name "Net-(VR3-A)") (class "Default")
      (node (ref "LCD1") (pin "17") (pinfunction "17_17") (pintype "passive"))
      (node (ref "VR3") (pin "1") (pinfunction "A_1") (pintype "passive"))
      (node (ref "VR3") (pin "2") (pinfunction "S_2") (pintype "passive"))
    )
    (net (code "65") (name "Net-(VR4-A)") (class "Default")
      (node (ref "LCD1") (pin "18") (pinfunction "18_18") (pintype "passive"))
      (node (ref "VR4") (pin "1") (pinfunction "A_1") (pintype "passive"))
      (node (ref "VR4") (pin "2") (pinfunction "S_2") (pintype "passive"))
    )
    (net (code "66") (name "RS") (class "Default")
      (node (ref "IC1") (pin "11") (pinfunction "GP1_11") (pintype "bidirectional"))
      (node (ref "LCD1") (pin "4") (pinfunction "4_4") (pintype "passive"))
    )
    (net (code "67") (name "unconnected-(H1-MOUNT-PadB3,2)") (class "Default")
      (node (ref "H1") (pin "B3,2") (pinfunction "MOUNT_B3,2") (pintype "passive"))
    )
    (net (code "68") (name "unconnected-(H2-MOUNT-PadB3,2)") (class "Default")
      (node (ref "H2") (pin "B3,2") (pinfunction "MOUNT_B3,2") (pintype "passive"))
    )
    (net (code "69") (name "unconnected-(H3-MOUNT-PadB3,2)") (class "Default")
      (node (ref "H3") (pin "B3,2") (pinfunction "MOUNT_B3,2") (pintype "passive"))
    )
    (net (code "70") (name "unconnected-(H4-MOUNT-PadB3,2)") (class "Default")
      (node (ref "H4") (pin "B3,2") (pinfunction "MOUNT_B3,2") (pintype "passive"))
    )
    (net (code "71") (name "unconnected-(IC1-GP0-Pad10)") (class "Default")
      (node (ref "IC1") (pin "10") (pinfunction "GP0_10") (pintype "bidirectional"))
    )
    (net (code "72") (name "unconnected-(IC1-GP7-Pad17)") (class "Default")
      (node (ref "IC1") (pin "17") (pinfunction "GP7_17") (pintype "bidirectional"))
    )
    (net (code "73") (name "unconnected-(IC1-INT-Pad8)") (class "Default")
      (node (ref "IC1") (pin "8") (pinfunction "INT_8") (pintype "output"))
    )
    (net (code "74") (name "unconnected-(LCD1-Pad7)") (class "Default")
      (node (ref "LCD1") (pin "7") (pinfunction "7_7") (pintype "passive"))
    )
    (net (code "75") (name "unconnected-(LCD1-Pad8)") (class "Default")
      (node (ref "LCD1") (pin "8") (pinfunction "8_8") (pintype "passive"))
    )
    (net (code "76") (name "unconnected-(LCD1-Pad9)") (class "Default")
      (node (ref "LCD1") (pin "9") (pinfunction "9_9") (pintype "passive"))
    )
    (net (code "77") (name "unconnected-(LCD1-Pad10)") (class "Default")
      (node (ref "LCD1") (pin "10") (pinfunction "10_10") (pintype "passive"))
    )
    (net (code "78") (name "unconnected-(U1-COM3{slash}KS2-PadP$5)") (class "Default")
      (node (ref "U1") (pin "P$5") (pinfunction "COM3/KS2_P$5") (pintype "bidirectional"))
    )
    (net (code "79") (name "unconnected-(U1-COM4-PadP$6)") (class "Default")
      (node (ref "U1") (pin "P$6") (pinfunction "COM4_P$6") (pintype "bidirectional"))
    )
    (net (code "80") (name "unconnected-(U1-COM5-PadP$7)") (class "Default")
      (node (ref "U1") (pin "P$7") (pinfunction "COM5_P$7") (pintype "bidirectional"))
    )
    (net (code "81") (name "unconnected-(U1-COM6-PadP$8)") (class "Default")
      (node (ref "U1") (pin "P$8") (pinfunction "COM6_P$8") (pintype "bidirectional"))
    )
    (net (code "82") (name "unconnected-(U1-COM7-PadP$9)") (class "Default")
      (node (ref "U1") (pin "P$9") (pinfunction "COM7_P$9") (pintype "bidirectional"))
    )
    (net (code "83") (name "unconnected-(U2-COM3{slash}KS2-PadP$5)") (class "Default")
      (node (ref "U2") (pin "P$5") (pinfunction "COM3/KS2_P$5") (pintype "bidirectional"))
    )
    (net (code "84") (name "unconnected-(U2-COM4-PadP$6)") (class "Default")
      (node (ref "U2") (pin "P$6") (pinfunction "COM4_P$6") (pintype "bidirectional"))
    )
    (net (code "85") (name "unconnected-(U2-COM5-PadP$7)") (class "Default")
      (node (ref "U2") (pin "P$7") (pinfunction "COM5_P$7") (pintype "bidirectional"))
    )
    (net (code "86") (name "unconnected-(U2-COM6-PadP$8)") (class "Default")
      (node (ref "U2") (pin "P$8") (pinfunction "COM6_P$8") (pintype "bidirectional"))
    )
    (net (code "87") (name "unconnected-(U2-COM7-PadP$9)") (class "Default")
      (node (ref "U2") (pin "P$9") (pinfunction "COM7_P$9") (pintype "bidirectional"))
    )
  )
)
